# participante.net
KiCad netlist of a schematic drawn in EAGLE
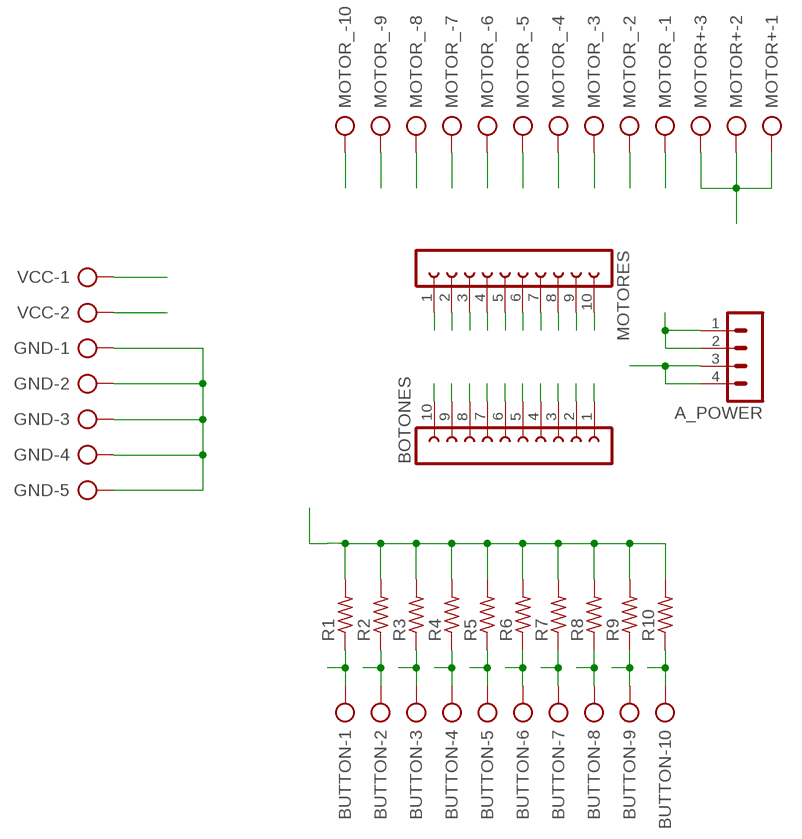
[diagram p0: schematic, sheet 1]
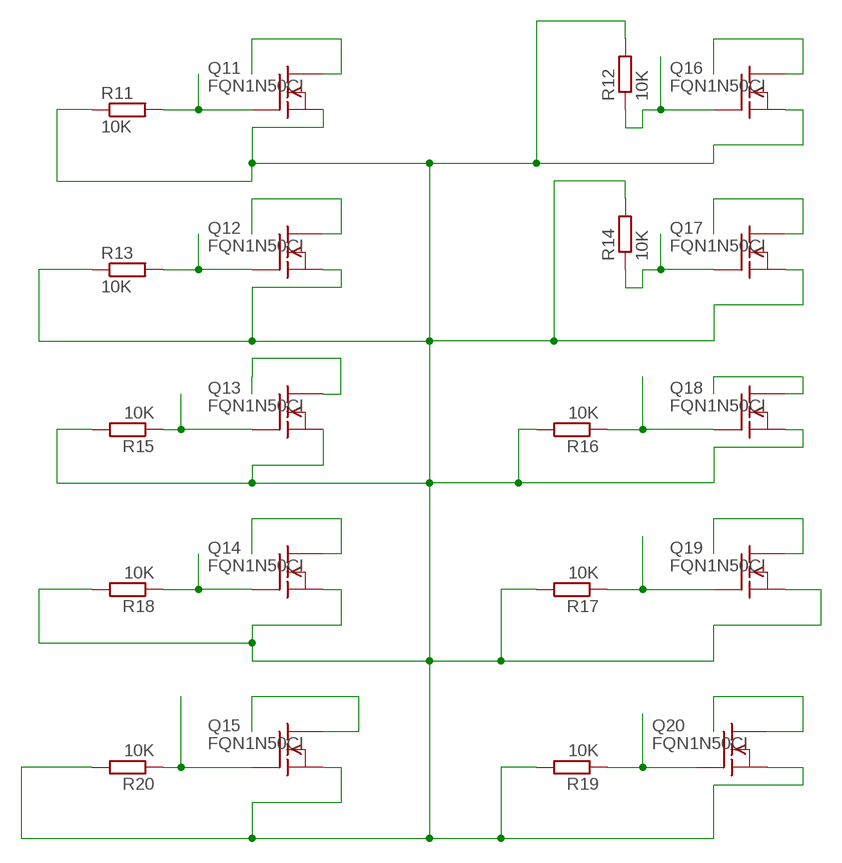
[diagram p1: schematic, sheet 2]
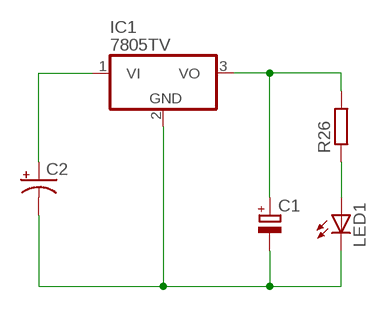
[diagram p2: schematic, sheet 3]

(export (version "E")
  (design (tool "Eeschema 10.0.6"))
  (components
    (comp (ref "Q11")
      (value "FQN1N50CI")
      (footprint "eagle-import:TO92-INLINE")
      (libsource (lib "eagle-import") (part "FQN1N50CI"))
    )
    (comp (ref "Q12")
      (value "FQN1N50CI")
      (footprint "eagle-import:TO92-INLINE")
      (libsource (lib "eagle-import") (part "FQN1N50CI"))
    )
    (comp (ref "Q13")
      (value "FQN1N50CI")
      (footprint "eagle-import:TO92-INLINE")
      (libsource (lib "eagle-import") (part "FQN1N50CI"))
    )
    (comp (ref "Q14")
      (value "FQN1N50CI")
      (footprint "eagle-import:TO92-INLINE")
      (libsource (lib "eagle-import") (part "FQN1N50CI"))
    )
    (comp (ref "Q15")
      (value "FQN1N50CI")
      (footprint "eagle-import:TO92-INLINE")
      (libsource (lib "eagle-import") (part "FQN1N50CI"))
    )
    (comp (ref "Q16")
      (value "FQN1N50CI")
      (footprint "eagle-import:TO92-INLINE")
      (libsource (lib "eagle-import") (part "FQN1N50CI"))
    )
    (comp (ref "Q17")
      (value "FQN1N50CI")
      (footprint "eagle-import:TO92-INLINE")
      (libsource (lib "eagle-import") (part "FQN1N50CI"))
    )
    (comp (ref "Q18")
      (value "FQN1N50CI")
      (footprint "eagle-import:TO92-INLINE")
      (libsource (lib "eagle-import") (part "FQN1N50CI"))
    )
    (comp (ref "Q19")
      (value "FQN1N50CI")
      (footprint "eagle-import:TO92-INLINE")
      (libsource (lib "eagle-import") (part "FQN1N50CI"))
    )
    (comp (ref "Q20")
      (value "FQN1N50CI")
      (footprint "eagle-import:TO92-INLINE")
      (libsource (lib "eagle-import") (part "FQN1N50CI"))
    )
    (comp (ref "R11")
      (value "10K")
      (footprint "eagle-import:0207_10")
      (libsource (lib "eagle-import") (part "R-EU_0207/10"))
    )
    (comp (ref "R12")
      (value "10K")
      (footprint "eagle-import:0207_10")
      (libsource (lib "eagle-import") (part "R-EU_0207/10"))
    )
    (comp (ref "R13")
      (value "10K")
      (footprint "eagle-import:0207_10")
      (libsource (lib "eagle-import") (part "R-EU_0207/10"))
    )
    (comp (ref "R14")
      (value "10K")
      (footprint "eagle-import:0207_10")
      (libsource (lib "eagle-import") (part "R-EU_0207/10"))
    )
    (comp (ref "R15")
      (value "10K")
      (footprint "eagle-import:0207_10")
      (libsource (lib "eagle-import") (part "R-EU_0207/10"))
    )
    (comp (ref "R16")
      (value "10K")
      (footprint "eagle-import:0207_10")
      (libsource (lib "eagle-import") (part "R-EU_0207/10"))
    )
    (comp (ref "R17")
      (value "10K")
      (footprint "eagle-import:0207_10")
      (libsource (lib "eagle-import") (part "R-EU_0207/10"))
    )
    (comp (ref "R18")
      (value "10K")
      (footprint "eagle-import:0207_10")
      (libsource (lib "eagle-import") (part "R-EU_0207/10"))
    )
    (comp (ref "R19")
      (value "10K")
      (footprint "eagle-import:0207_10")
      (libsource (lib "eagle-import") (part "R-EU_0207/10"))
    )
    (comp (ref "R20")
      (value "10K")
      (footprint "eagle-import:0207_10")
      (libsource (lib "eagle-import") (part "R-EU_0207/10"))
    )
    (comp (ref "C1")
      (value "CPOL-EUE2.5-6")
      (footprint "eagle-import:E2,5-6")
      (libsource (lib "eagle-import") (part "CPOL-EUE2.5-6"))
    )
    (comp (ref "C2")
      (value "CPOL-USE3.5-8")
      (footprint "eagle-import:E3,5-8")
      (libsource (lib "eagle-import") (part "CPOL-USE3.5-8"))
    )
    (comp (ref "IC1")
      (value "7805TV")
      (footprint "eagle-import:TO220V")
      (libsource (lib "eagle-import") (part "78TV05"))
    )
    (comp (ref "LED1")
      (value "LED5MM")
      (footprint "eagle-import:LED5MM")
      (libsource (lib "eagle-import") (part "LED5MM"))
    )
    (comp (ref "R26")
      (value "R-EU_0207/10")
      (footprint "eagle-import:0207_10")
      (libsource (lib "eagle-import") (part "R-EU_0207/10"))
    )
    (comp (ref "A_POWER")
      (value "MA04-1")
      (footprint "eagle-import:MA04-1")
      (libsource (lib "eagle-import") (part "MA04-1"))
    )
    (comp (ref "BOTONES")
      (value "FE10-1")
      (footprint "eagle-import:FE10")
      (libsource (lib "eagle-import") (part "FE10-1"))
    )
    (comp (ref "BUTTON")
      (value "AK300/10")
      (footprint "eagle-import:AK300_10")
      (libsource (lib "eagle-import") (part "AK300/10"))
    )
    (comp (ref "GND")
      (value "AK300/5")
      (footprint "eagle-import:AK300_5")
      (libsource (lib "eagle-import") (part "AK300/5"))
    )
    (comp (ref "MOTOR+")
      (value "AK300/3")
      (footprint "eagle-import:AK300_3")
      (libsource (lib "eagle-import") (part "AK300/3"))
    )
    (comp (ref "MOTORES")
      (value "FE10-1")
      (footprint "eagle-import:FE10")
      (libsource (lib "eagle-import") (part "FE10-1"))
    )
    (comp (ref "MOTOR_")
      (value "AK300/10")
      (footprint "eagle-import:AK300_10")
      (libsource (lib "eagle-import") (part "AK300/10"))
    )
    (comp (ref "R1")
      (value "R-US_0204/7")
      (footprint "eagle-import:0204_7")
      (libsource (lib "eagle-import") (part "R-US_0204/7"))
    )
    (comp (ref "R2")
      (value "R-US_0204/7")
      (footprint "eagle-import:0204_7")
      (libsource (lib "eagle-import") (part "R-US_0204/7"))
    )
    (comp (ref "R3")
      (value "R-US_0204/7")
      (footprint "eagle-import:0204_7")
      (libsource (lib "eagle-import") (part "R-US_0204/7"))
    )
    (comp (ref "R4")
      (value "R-US_0204/7")
      (footprint "eagle-import:0204_7")
      (libsource (lib "eagle-import") (part "R-US_0204/7"))
    )
    (comp (ref "R5")
      (value "R-US_0204/7")
      (footprint "eagle-import:0204_7")
      (libsource (lib "eagle-import") (part "R-US_0204/7"))
    )
    (comp (ref "R6")
      (value "R-US_0204/7")
      (footprint "eagle-import:0204_7")
      (libsource (lib "eagle-import") (part "R-US_0204/7"))
    )
    (comp (ref "R7")
      (value "R-US_0204/7")
      (footprint "eagle-import:0204_7")
      (libsource (lib "eagle-import") (part "R-US_0204/7"))
    )
    (comp (ref "R8")
      (value "R-US_0204/7")
      (footprint "eagle-import:0204_7")
      (libsource (lib "eagle-import") (part "R-US_0204/7"))
    )
    (comp (ref "R9")
      (value "R-US_0204/7")
      (footprint "eagle-import:0204_7")
      (libsource (lib "eagle-import") (part "R-US_0204/7"))
    )
    (comp (ref "R10")
      (value "R-US_0204/7")
      (footprint "eagle-import:0204_7")
      (libsource (lib "eagle-import") (part "R-US_0204/7"))
    )
    (comp (ref "VCC")
      (value "AK300/2")
      (footprint "eagle-import:AK300_2")
      (libsource (lib "eagle-import") (part "AK300/2"))
    )
  )
  (nets
    (net (code "1") (name "5VDC") (class "Default")
      (node (ref "C1") (pin "+") (pinfunction "+_+") (pintype "passive"))
      (node (ref "IC1") (pin "3") (pinfunction "VO_3") (pintype "passive"))
      (node (ref "R1") (pin "2") (pinfunction "2_2") (pintype "passive"))
      (node (ref "R10") (pin "2") (pinfunction "2_2") (pintype "passive"))
      (node (ref "R2") (pin "2") (pinfunction "2_2") (pintype "passive"))
      (node (ref "R26") (pin "2") (pinfunction "2_2") (pintype "passive"))
      (node (ref "R3") (pin "2") (pinfunction "2_2") (pintype "passive"))
      (node (ref "R4") (pin "2") (pinfunction "2_2") (pintype "passive"))
      (node (ref "R5") (pin "2") (pinfunction "2_2") (pintype "passive"))
      (node (ref "R6") (pin "2") (pinfunction "2_2") (pintype "passive"))
      (node (ref "R7") (pin "2") (pinfunction "2_2") (pintype "passive"))
      (node (ref "R8") (pin "2") (pinfunction "2_2") (pintype "passive"))
      (node (ref "R9") (pin "2") (pinfunction "2_2") (pintype "passive"))
    )
    (net (code "2") (name "A22") (class "Default")
      (node (ref "BOTONES") (pin "1") (pinfunction "1_1") (pintype "passive"))
      (node (ref "BUTTON") (pin "1") (pinfunction "KL_1") (pintype "passive"))
      (node (ref "R1") (pin "1") (pinfunction "1_1") (pintype "passive"))
    )
    (net (code "3") (name "A23") (class "Default")
      (node (ref "BOTONES") (pin "2") (pinfunction "2_2") (pintype "passive"))
      (node (ref "BUTTON") (pin "2") (pinfunction "KL_2") (pintype "passive"))
      (node (ref "R2") (pin "1") (pinfunction "1_1") (pintype "passive"))
    )
    (net (code "4") (name "A24") (class "Default")
      (node (ref "BOTONES") (pin "3") (pinfunction "3_3") (pintype "passive"))
      (node (ref "BUTTON") (pin "3") (pinfunction "KL_3") (pintype "passive"))
      (node (ref "R3") (pin "1") (pinfunction "1_1") (pintype "passive"))
    )
    (net (code "5") (name "A25") (class "Default")
      (node (ref "BOTONES") (pin "4") (pinfunction "4_4") (pintype "passive"))
      (node (ref "BUTTON") (pin "4") (pinfunction "KL_4") (pintype "passive"))
      (node (ref "R4") (pin "1") (pinfunction "1_1") (pintype "passive"))
    )
    (net (code "6") (name "A26") (class "Default")
      (node (ref "BOTONES") (pin "5") (pinfunction "5_5") (pintype "passive"))
      (node (ref "BUTTON") (pin "5") (pinfunction "KL_5") (pintype "passive"))
      (node (ref "R5") (pin "1") (pinfunction "1_1") (pintype "passive"))
    )
    (net (code "7") (name "A27") (class "Default")
      (node (ref "BOTONES") (pin "6") (pinfunction "6_6") (pintype "passive"))
      (node (ref "BUTTON") (pin "6") (pinfunction "KL_6") (pintype "passive"))
      (node (ref "R6") (pin "1") (pinfunction "1_1") (pintype "passive"))
    )
    (net (code "8") (name "A28") (class "Default")
      (node (ref "BOTONES") (pin "7") (pinfunction "7_7") (pintype "passive"))
      (node (ref "BUTTON") (pin "7") (pinfunction "KL_7") (pintype "passive"))
      (node (ref "R7") (pin "1") (pinfunction "1_1") (pintype "passive"))
    )
    (net (code "9") (name "A29") (class "Default")
      (node (ref "BOTONES") (pin "8") (pinfunction "8_8") (pintype "passive"))
      (node (ref "BUTTON") (pin "8") (pinfunction "KL_8") (pintype "passive"))
      (node (ref "R8") (pin "1") (pinfunction "1_1") (pintype "passive"))
    )
    (net (code "10") (name "A30") (class "Default")
      (node (ref "BOTONES") (pin "9") (pinfunction "9_9") (pintype "passive"))
      (node (ref "BUTTON") (pin "9") (pinfunction "KL_9") (pintype "passive"))
      (node (ref "R9") (pin "1") (pinfunction "1_1") (pintype "passive"))
    )
    (net (code "11") (name "A31") (class "Default")
      (node (ref "BOTONES") (pin "10") (pinfunction "10_10") (pintype "passive"))
      (node (ref "BUTTON") (pin "10") (pinfunction "KL_10") (pintype "passive"))
      (node (ref "R10") (pin "1") (pinfunction "1_1") (pintype "passive"))
    )
    (net (code "12") (name "AM_1") (class "Default")
      (node (ref "MOTORES") (pin "1") (pinfunction "1_1") (pintype "passive"))
      (node (ref "Q11") (pin "2") (pinfunction "G_2") (pintype "passive"))
      (node (ref "R11") (pin "2") (pinfunction "2_2") (pintype "passive"))
    )
    (net (code "13") (name "AM_2") (class "Default")
      (node (ref "MOTORES") (pin "2") (pinfunction "2_2") (pintype "passive"))
      (node (ref "Q12") (pin "2") (pinfunction "G_2") (pintype "passive"))
      (node (ref "R13") (pin "2") (pinfunction "2_2") (pintype "passive"))
    )
    (net (code "14") (name "AM_3") (class "Default")
      (node (ref "MOTORES") (pin "3") (pinfunction "3_3") (pintype "passive"))
      (node (ref "Q13") (pin "2") (pinfunction "G_2") (pintype "passive"))
      (node (ref "R15") (pin "1") (pinfunction "1_1") (pintype "passive"))
    )
    (net (code "15") (name "AM_4") (class "Default")
      (node (ref "MOTORES") (pin "4") (pinfunction "4_4") (pintype "passive"))
      (node (ref "Q14") (pin "2") (pinfunction "G_2") (pintype "passive"))
      (node (ref "R18") (pin "1") (pinfunction "1_1") (pintype "passive"))
    )
    (net (code "16") (name "AM_5") (class "Default")
      (node (ref "MOTORES") (pin "5") (pinfunction "5_5") (pintype "passive"))
      (node (ref "Q15") (pin "2") (pinfunction "G_2") (pintype "passive"))
      (node (ref "R20") (pin "1") (pinfunction "1_1") (pintype "passive"))
    )
    (net (code "17") (name "AM_6") (class "Default")
      (node (ref "MOTORES") (pin "6") (pinfunction "6_6") (pintype "passive"))
      (node (ref "Q20") (pin "2") (pinfunction "G_2") (pintype "passive"))
      (node (ref "R19") (pin "1") (pinfunction "1_1") (pintype "passive"))
    )
    (net (code "18") (name "AM_7") (class "Default")
      (node (ref "MOTORES") (pin "7") (pinfunction "7_7") (pintype "passive"))
      (node (ref "Q19") (pin "2") (pinfunction "G_2") (pintype "passive"))
      (node (ref "R17") (pin "1") (pinfunction "1_1") (pintype "passive"))
    )
    (net (code "19") (name "AM_8") (class "Default")
      (node (ref "MOTORES") (pin "8") (pinfunction "8_8") (pintype "passive"))
      (node (ref "Q18") (pin "2") (pinfunction "G_2") (pintype "passive"))
      (node (ref "R16") (pin "1") (pinfunction "1_1") (pintype "passive"))
    )
    (net (code "20") (name "AM_9") (class "Default")
      (node (ref "MOTORES") (pin "9") (pinfunction "9_9") (pintype "passive"))
      (node (ref "Q17") (pin "2") (pinfunction "G_2") (pintype "passive"))
      (node (ref "R14") (pin "1") (pinfunction "1_1") (pintype "passive"))
    )
    (net (code "21") (name "AM_10") (class "Default")
      (node (ref "MOTORES") (pin "10") (pinfunction "10_10") (pintype "passive"))
      (node (ref "Q16") (pin "2") (pinfunction "G_2") (pintype "passive"))
      (node (ref "R12") (pin "1") (pinfunction "1_1") (pintype "passive"))
    )
    (net (code "22") (name "GND") (class "Default")
      (node (ref "A_POWER") (pin "1") (pinfunction "1_1") (pintype "passive"))
      (node (ref "A_POWER") (pin "2") (pinfunction "2_2") (pintype "passive"))
      (node (ref "C1") (pin "-") (pinfunction "-_-") (pintype "passive"))
      (node (ref "C2") (pin "-") (pinfunction "-_-") (pintype "passive"))
      (node (ref "GND") (pin "1") (pinfunction "KL_1") (pintype "passive"))
      (node (ref "GND") (pin "2") (pinfunction "KL_2") (pintype "passive"))
      (node (ref "GND") (pin "3") (pinfunction "KL_3") (pintype "passive"))
      (node (ref "GND") (pin "4") (pinfunction "KL_4") (pintype "passive"))
      (node (ref "GND") (pin "5") (pinfunction "KL_5") (pintype "passive"))
      (node (ref "IC1") (pin "2") (pinfunction "GND_2") (pintype "passive"))
      (node (ref "LED1") (pin "K") (pinfunction "C_K") (pintype "passive"))
      (node (ref "Q11") (pin "3") (pinfunction "S_3") (pintype "passive"))
      (node (ref "Q12") (pin "3") (pinfunction "S_3") (pintype "passive"))
      (node (ref "Q13") (pin "3") (pinfunction "S_3") (pintype "passive"))
      (node (ref "Q14") (pin "3") (pinfunction "S_3") (pintype "passive"))
      (node (ref "Q15") (pin "3") (pinfunction "S_3") (pintype "passive"))
      (node (ref "Q16") (pin "3") (pinfunction "S_3") (pintype "passive"))
      (node (ref "Q17") (pin "3") (pinfunction "S_3") (pintype "passive"))
      (node (ref "Q18") (pin "3") (pinfunction "S_3") (pintype "passive"))
      (node (ref "Q19") (pin "3") (pinfunction "S_3") (pintype "passive"))
      (node (ref "Q20") (pin "3") (pinfunction "S_3") (pintype "passive"))
      (node (ref "R11") (pin "1") (pinfunction "1_1") (pintype "passive"))
      (node (ref "R12") (pin "2") (pinfunction "2_2") (pintype "passive"))
      (node (ref "R13") (pin "1") (pinfunction "1_1") (pintype "passive"))
      (node (ref "R14") (pin "2") (pinfunction "2_2") (pintype "passive"))
      (node (ref "R15") (pin "2") (pinfunction "2_2") (pintype "passive"))
      (node (ref "R16") (pin "2") (pinfunction "2_2") (pintype "passive"))
      (node (ref "R17") (pin "2") (pinfunction "2_2") (pintype "passive"))
      (node (ref "R18") (pin "2") (pinfunction "2_2") (pintype "passive"))
      (node (ref "R19") (pin "2") (pinfunction "2_2") (pintype "passive"))
      (node (ref "R20") (pin "2") (pinfunction "2_2") (pintype "passive"))
    )
    (net (code "23") (name "M_N1") (class "Default")
      (node (ref "MOTOR_") (pin "1") (pinfunction "KL_1") (pintype "passive"))
      (node (ref "Q11") (pin "1") (pinfunction "D_1") (pintype "passive"))
    )
    (net (code "24") (name "M_N2") (class "Default")
      (node (ref "MOTOR_") (pin "2") (pinfunction "KL_2") (pintype "passive"))
      (node (ref "Q12") (pin "1") (pinfunction "D_1") (pintype "passive"))
    )
    (net (code "25") (name "M_N3") (class "Default")
      (node (ref "MOTOR_") (pin "3") (pinfunction "KL_3") (pintype "passive"))
      (node (ref "Q13") (pin "1") (pinfunction "D_1") (pintype "passive"))
    )
    (net (code "26") (name "M_N4") (class "Default")
      (node (ref "MOTOR_") (pin "4") (pinfunction "KL_4") (pintype "passive"))
      (node (ref "Q14") (pin "1") (pinfunction "D_1") (pintype "passive"))
    )
    (net (code "27") (name "M_N5") (class "Default")
      (node (ref "MOTOR_") (pin "5") (pinfunction "KL_5") (pintype "passive"))
      (node (ref "Q15") (pin "1") (pinfunction "D_1") (pintype "passive"))
    )
    (net (code "28") (name "M_N6") (class "Default")
      (node (ref "MOTOR_") (pin "6") (pinfunction "KL_6") (pintype "passive"))
      (node (ref "Q16") (pin "1") (pinfunction "D_1") (pintype "passive"))
    )
    (net (code "29") (name "M_N7") (class "Default")
      (node (ref "MOTOR_") (pin "7") (pinfunction "KL_7") (pintype "passive"))
      (node (ref "Q17") (pin "1") (pinfunction "D_1") (pintype "passive"))
    )
    (net (code "30") (name "M_N8") (class "Default")
      (node (ref "MOTOR_") (pin "8") (pinfunction "KL_8") (pintype "passive"))
      (node (ref "Q18") (pin "1") (pinfunction "D_1") (pintype "passive"))
    )
    (net (code "31") (name "M_N9") (class "Default")
      (node (ref "MOTOR_") (pin "9") (pinfunction "KL_9") (pintype "passive"))
      (node (ref "Q19") (pin "1") (pinfunction "D_1") (pintype "passive"))
    )
    (net (code "32") (name "M_N10") (class "Default")
      (node (ref "MOTOR_") (pin "10") (pinfunction "KL_10") (pintype "passive"))
      (node (ref "Q20") (pin "1") (pinfunction "D_1") (pintype "passive"))
    )
    (net (code "33") (name "Net-(LED1-PadA)") (class "Default")
      (node (ref "LED1") (pin "A") (pinfunction "A_A") (pintype "passive"))
      (node (ref "R26") (pin "1") (pinfunction "1_1") (pintype "passive"))
    )
    (net (code "34") (name "VCC") (class "Default")
      (node (ref "C2") (pin "+") (pinfunction "+_+") (pintype "passive"))
      (node (ref "IC1") (pin "1") (pinfunction "VI_1") (pintype "input"))
      (node (ref "MOTOR+") (pin "1") (pinfunction "KL_1") (pintype "passive"))
      (node (ref "MOTOR+") (pin "2") (pinfunction "KL_2") (pintype "passive"))
      (node (ref "MOTOR+") (pin "3") (pinfunction "KL_3") (pintype "passive"))
      (node (ref "VCC") (pin "2") (pinfunction "KL_2") (pintype "passive"))
    )
    (net (code "35") (name "VCC_A") (class "Default")
      (node (ref "A_POWER") (pin "3") (pinfunction "3_3") (pintype "passive"))
      (node (ref "A_POWER") (pin "4") (pinfunction "4_4") (pintype "passive"))
      (node (ref "VCC") (pin "1") (pinfunction "KL_1") (pintype "passive"))
    )
  )
)
